# NodeMCU_Watering_System_III.net
KiCad netlist of a schematic drawn in EAGLE
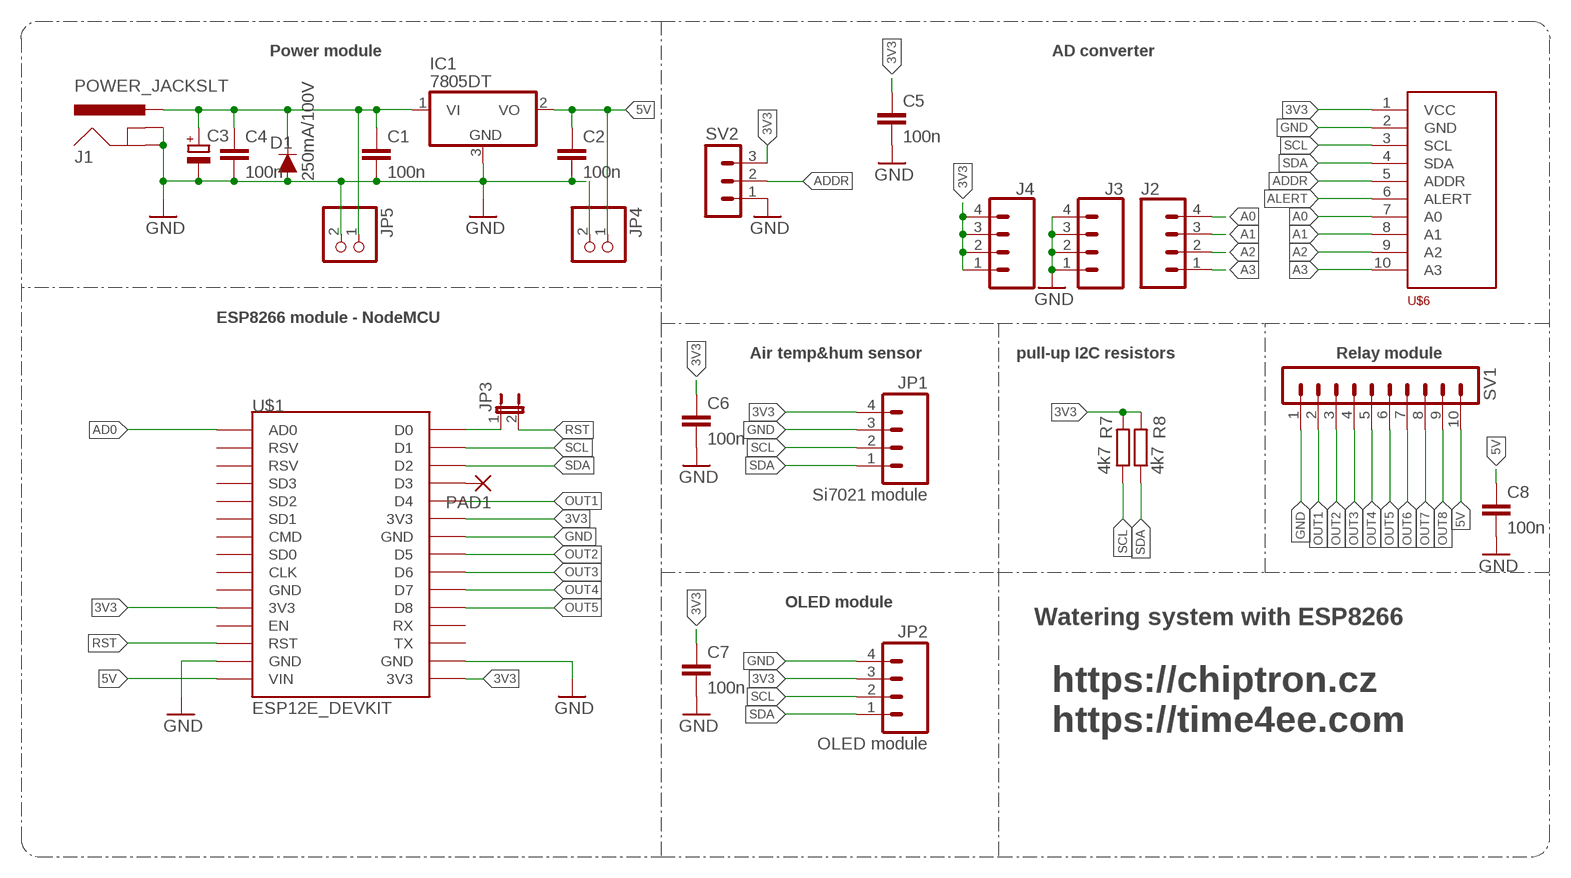
[diagram p0: schematic, sheet 1]

(export (version "E")
  (design (tool "Eeschema 10.0.6"))
  (components
    (comp (ref "C1")
      (value "100n")
      (footprint "eagle-import:C0805K")
      (libsource (lib "eagle-import") (part "C-EUC0805K"))
    )
    (comp (ref "C2")
      (value "100n")
      (footprint "eagle-import:C0805K")
      (libsource (lib "eagle-import") (part "C-EUC0805K"))
    )
    (comp (ref "C3")
      (value "CPOL-EUB/3528-21W")
      (footprint "eagle-import:B_3528-21W")
      (libsource (lib "eagle-import") (part "CPOL-EUB/3528-21W"))
    )
    (comp (ref "C4")
      (value "100n")
      (footprint "eagle-import:C0805K")
      (libsource (lib "eagle-import") (part "C-EUC0805K"))
    )
    (comp (ref "C5")
      (value "100n")
      (footprint "eagle-import:C0805K")
      (libsource (lib "eagle-import") (part "C-EUC0805K"))
    )
    (comp (ref "C6")
      (value "100n")
      (footprint "eagle-import:C0805K")
      (libsource (lib "eagle-import") (part "C-EUC0805K"))
    )
    (comp (ref "C7")
      (value "100n")
      (footprint "eagle-import:C0805K")
      (libsource (lib "eagle-import") (part "C-EUC0805K"))
    )
    (comp (ref "C8")
      (value "100n")
      (footprint "eagle-import:C0805K")
      (libsource (lib "eagle-import") (part "C-EUC0805K"))
    )
    (comp (ref "D1")
      (value "250mA/100V")
      (footprint "eagle-import:SOD-323")
      (libsource (lib "eagle-import") (part "DIODE-BAS16J"))
    )
    (comp (ref "IC1")
      (value "7805DT")
      (footprint "eagle-import:TO252")
      (libsource (lib "eagle-import") (part "78DT05"))
    )
    (comp (ref "J1")
      (value "POWER_JACKSLT")
      (footprint "eagle-import:POWER_JACK_SLOT")
      (libsource (lib "eagle-import") (part "POWER_JACKSLT"))
    )
    (comp (ref "J2")
      (value "CONN_04")
      (footprint "eagle-import:1X04")
      (libsource (lib "eagle-import") (part "CONN_04"))
    )
    (comp (ref "J3")
      (value "CONN_04")
      (footprint "eagle-import:1X04")
      (libsource (lib "eagle-import") (part "CONN_04"))
    )
    (comp (ref "J4")
      (value "CONN_04")
      (footprint "eagle-import:1X04")
      (libsource (lib "eagle-import") (part "CONN_04"))
    )
    (comp (ref "JP1")
      (value "Si7021 module")
      (footprint "eagle-import:1X04_LONGPADS")
      (libsource (lib "eagle-import") (part "M04LONGPADS"))
    )
    (comp (ref "JP2")
      (value "OLED module")
      (footprint "eagle-import:1X04_LONGPADS")
      (libsource (lib "eagle-import") (part "M04LONGPADS"))
    )
    (comp (ref "JP3")
      (value "JP1E")
      (footprint "eagle-import:JP1")
      (libsource (lib "eagle-import") (part "JP1E"))
    )
    (comp (ref "JP4")
      (value "PINHD-1X2")
      (footprint "eagle-import:1X02")
      (libsource (lib "eagle-import") (part "PINHD-1X2"))
    )
    (comp (ref "JP5")
      (value "PINHD-1X2")
      (footprint "eagle-import:1X02")
      (libsource (lib "eagle-import") (part "PINHD-1X2"))
    )
    (comp (ref "PAD1")
      (value "1,6/0,8")
      (footprint "eagle-import:1,6_0,8")
      (libsource (lib "eagle-import") (part "1,6/0,8"))
    )
    (comp (ref "R7")
      (value "4k7")
      (footprint "eagle-import:M0805")
      (libsource (lib "eagle-import") (part "R-EU_M0805"))
    )
    (comp (ref "R8")
      (value "4k7")
      (footprint "eagle-import:M0805")
      (libsource (lib "eagle-import") (part "R-EU_M0805"))
    )
    (comp (ref "SV1")
      (value "MA10-1")
      (footprint "eagle-import:MA10-1")
      (libsource (lib "eagle-import") (part "MA10-1"))
    )
    (comp (ref "SV2")
      (value "MA03-1")
      (footprint "eagle-import:MA03-1")
      (libsource (lib "eagle-import") (part "MA03-1"))
    )
    (comp (ref "U$1")
      (value "ESP12E_DEVKIT")
      (footprint "eagle-import:ESP12E_DEVKIT")
      (libsource (lib "eagle-import") (part "ESP12E_DEVKIT"))
    )
    (comp (ref "U$6")
      (value "ADS1115_BOARD")
      (footprint "eagle-import:ADS1115_ADS")
      (libsource (lib "eagle-import") (part "ADS1115_BOARD"))
    )
  )
  (nets
    (net (code "1") (name "3V3") (class "Default")
      (node (ref "C5") (pin "1") (pinfunction "1_1") (pintype "passive"))
      (node (ref "C6") (pin "1") (pinfunction "1_1") (pintype "passive"))
      (node (ref "C7") (pin "1") (pinfunction "1_1") (pintype "passive"))
      (node (ref "J4") (pin "1") (pinfunction "1_1") (pintype "passive"))
      (node (ref "J4") (pin "2") (pinfunction "2_2") (pintype "passive"))
      (node (ref "J4") (pin "3") (pinfunction "3_3") (pintype "passive"))
      (node (ref "J4") (pin "4") (pinfunction "4_4") (pintype "passive"))
      (node (ref "JP1") (pin "4") (pinfunction "4_4") (pintype "passive"))
      (node (ref "JP2") (pin "3") (pinfunction "3_3") (pintype "passive"))
      (node (ref "R7") (pin "2") (pinfunction "2_2") (pintype "passive"))
      (node (ref "R8") (pin "2") (pinfunction "2_2") (pintype "passive"))
      (node (ref "SV2") (pin "3") (pinfunction "3_3") (pintype "passive"))
      (node (ref "U$1") (pin "3V3@0") (pinfunction "3V3_3V3@0") (pintype "bidirectional"))
      (node (ref "U$1") (pin "3V3@1") (pinfunction "3V3_3V3@1") (pintype "bidirectional"))
      (node (ref "U$1") (pin "3V3@2") (pinfunction "3V3_3V3@2") (pintype "bidirectional"))
      (node (ref "U$6") (pin "1") (pinfunction "VCC_1") (pintype "bidirectional"))
    )
    (net (code "2") (name "5V") (class "Default")
      (node (ref "C2") (pin "1") (pinfunction "1_1") (pintype "passive"))
      (node (ref "C8") (pin "1") (pinfunction "1_1") (pintype "passive"))
      (node (ref "IC1") (pin "2") (pinfunction "VO_2") (pintype "passive"))
      (node (ref "JP4") (pin "1") (pinfunction "1_1") (pintype "passive"))
      (node (ref "SV1") (pin "10") (pinfunction "10_10") (pintype "passive"))
      (node (ref "U$1") (pin "VIN") (pinfunction "VIN_VIN") (pintype "bidirectional"))
    )
    (net (code "3") (name "A0") (class "Default")
      (node (ref "J2") (pin "4") (pinfunction "4_4") (pintype "passive"))
      (node (ref "U$6") (pin "7") (pinfunction "A0_7") (pintype "bidirectional"))
    )
    (net (code "4") (name "A1") (class "Default")
      (node (ref "J2") (pin "3") (pinfunction "3_3") (pintype "passive"))
      (node (ref "U$6") (pin "8") (pinfunction "A1_8") (pintype "bidirectional"))
    )
    (net (code "5") (name "A2") (class "Default")
      (node (ref "J2") (pin "2") (pinfunction "2_2") (pintype "passive"))
      (node (ref "U$6") (pin "9") (pinfunction "A2_9") (pintype "bidirectional"))
    )
    (net (code "6") (name "A3") (class "Default")
      (node (ref "J2") (pin "1") (pinfunction "1_1") (pintype "passive"))
      (node (ref "U$6") (pin "10") (pinfunction "A3_10") (pintype "bidirectional"))
    )
    (net (code "7") (name "AD0") (class "Default")
      (node (ref "U$1") (pin "AD0") (pinfunction "AD0_AD0") (pintype "bidirectional"))
    )
    (net (code "8") (name "ADDR") (class "Default")
      (node (ref "SV2") (pin "2") (pinfunction "2_2") (pintype "passive"))
      (node (ref "U$6") (pin "5") (pinfunction "ADDR_5") (pintype "bidirectional"))
    )
    (net (code "9") (name "ALERT") (class "Default")
      (node (ref "U$6") (pin "6") (pinfunction "ALERT_6") (pintype "bidirectional"))
    )
    (net (code "10") (name "GND") (class "Default")
      (node (ref "C1") (pin "2") (pinfunction "2_2") (pintype "passive"))
      (node (ref "C2") (pin "2") (pinfunction "2_2") (pintype "passive"))
      (node (ref "C3") (pin "-") (pinfunction "-_-") (pintype "passive"))
      (node (ref "C4") (pin "2") (pinfunction "2_2") (pintype "passive"))
      (node (ref "C5") (pin "2") (pinfunction "2_2") (pintype "passive"))
      (node (ref "C6") (pin "2") (pinfunction "2_2") (pintype "passive"))
      (node (ref "C7") (pin "2") (pinfunction "2_2") (pintype "passive"))
      (node (ref "C8") (pin "2") (pinfunction "2_2") (pintype "passive"))
      (node (ref "D1") (pin "A") (pinfunction "A_A") (pintype "passive"))
      (node (ref "IC1") (pin "3") (pinfunction "GND_3") (pintype "passive"))
      (node (ref "J1") (pin "GND@1") (pinfunction "GNDBREAK_GND@1") (pintype "bidirectional"))
      (node (ref "J1") (pin "GND@2") (pinfunction "GND_GND@2") (pintype "bidirectional"))
      (node (ref "J3") (pin "1") (pinfunction "1_1") (pintype "passive"))
      (node (ref "J3") (pin "2") (pinfunction "2_2") (pintype "passive"))
      (node (ref "J3") (pin "3") (pinfunction "3_3") (pintype "passive"))
      (node (ref "J3") (pin "4") (pinfunction "4_4") (pintype "passive"))
      (node (ref "JP1") (pin "3") (pinfunction "3_3") (pintype "passive"))
      (node (ref "JP2") (pin "4") (pinfunction "4_4") (pintype "passive"))
      (node (ref "JP4") (pin "2") (pinfunction "2_2") (pintype "passive"))
      (node (ref "JP5") (pin "2") (pinfunction "2_2") (pintype "passive"))
      (node (ref "SV1") (pin "1") (pinfunction "1_1") (pintype "passive"))
      (node (ref "SV2") (pin "1") (pinfunction "1_1") (pintype "passive"))
      (node (ref "U$1") (pin "GND@1") (pinfunction "GND_GND@1") (pintype "bidirectional"))
      (node (ref "U$1") (pin "GND@2") (pinfunction "GND_GND@2") (pintype "bidirectional"))
      (node (ref "U$1") (pin "GND@3") (pinfunction "GND_GND@3") (pintype "bidirectional"))
      (node (ref "U$6") (pin "2") (pinfunction "GND_2") (pintype "bidirectional"))
    )
    (net (code "11") (name "Net-(IC1-VI)") (class "Default")
      (node (ref "C1") (pin "1") (pinfunction "1_1") (pintype "passive"))
      (node (ref "C3") (pin "+") (pinfunction "+_+") (pintype "passive"))
      (node (ref "C4") (pin "1") (pinfunction "1_1") (pintype "passive"))
      (node (ref "D1") (pin "C") (pinfunction "C_C") (pintype "passive"))
      (node (ref "IC1") (pin "1") (pinfunction "VI_1") (pintype "input"))
      (node (ref "J1") (pin "PWR") (pinfunction "PWR_PWR") (pintype "bidirectional"))
      (node (ref "JP5") (pin "1") (pinfunction "1_1") (pintype "passive"))
    )
    (net (code "12") (name "Net-(JP3-Pad1)") (class "Default")
      (node (ref "JP3") (pin "1") (pinfunction "1_1") (pintype "passive"))
      (node (ref "U$1") (pin "D0") (pinfunction "D0_D0") (pintype "bidirectional"))
    )
    (net (code "13") (name "Net-(PAD1-P)") (class "Default")
      (node (ref "PAD1") (pin "1") (pinfunction "P_1") (pintype "passive"))
      (node (ref "U$1") (pin "D3") (pinfunction "D3_D3") (pintype "bidirectional"))
    )
    (net (code "14") (name "OUT1") (class "Default")
      (node (ref "SV1") (pin "2") (pinfunction "2_2") (pintype "passive"))
      (node (ref "U$1") (pin "D4") (pinfunction "D4_D4") (pintype "bidirectional"))
    )
    (net (code "15") (name "OUT2") (class "Default")
      (node (ref "SV1") (pin "3") (pinfunction "3_3") (pintype "passive"))
      (node (ref "U$1") (pin "D5") (pinfunction "D5_D5") (pintype "bidirectional"))
    )
    (net (code "16") (name "OUT3") (class "Default")
      (node (ref "SV1") (pin "4") (pinfunction "4_4") (pintype "passive"))
      (node (ref "U$1") (pin "D6") (pinfunction "D6_D6") (pintype "bidirectional"))
    )
    (net (code "17") (name "OUT4") (class "Default")
      (node (ref "SV1") (pin "5") (pinfunction "5_5") (pintype "passive"))
      (node (ref "U$1") (pin "D7") (pinfunction "D7_D7") (pintype "bidirectional"))
    )
    (net (code "18") (name "OUT5") (class "Default")
      (node (ref "SV1") (pin "6") (pinfunction "6_6") (pintype "passive"))
      (node (ref "U$1") (pin "D8") (pinfunction "D8_D8") (pintype "bidirectional"))
    )
    (net (code "19") (name "OUT6") (class "Default")
      (node (ref "SV1") (pin "7") (pinfunction "7_7") (pintype "passive"))
    )
    (net (code "20") (name "OUT7") (class "Default")
      (node (ref "SV1") (pin "8") (pinfunction "8_8") (pintype "passive"))
    )
    (net (code "21") (name "OUT8") (class "Default")
      (node (ref "SV1") (pin "9") (pinfunction "9_9") (pintype "passive"))
    )
    (net (code "22") (name "RST") (class "Default")
      (node (ref "JP3") (pin "2") (pinfunction "2_2") (pintype "passive"))
      (node (ref "U$1") (pin "RST") (pinfunction "RST_RST") (pintype "bidirectional"))
    )
    (net (code "23") (name "SCL") (class "Default")
      (node (ref "JP1") (pin "2") (pinfunction "2_2") (pintype "passive"))
      (node (ref "JP2") (pin "2") (pinfunction "2_2") (pintype "passive"))
      (node (ref "R7") (pin "1") (pinfunction "1_1") (pintype "passive"))
      (node (ref "U$1") (pin "D1") (pinfunction "D1_D1") (pintype "bidirectional"))
      (node (ref "U$6") (pin "3") (pinfunction "SCL_3") (pintype "bidirectional"))
    )
    (net (code "24") (name "SDA") (class "Default")
      (node (ref "JP1") (pin "1") (pinfunction "1_1") (pintype "passive"))
      (node (ref "JP2") (pin "1") (pinfunction "1_1") (pintype "passive"))
      (node (ref "R8") (pin "1") (pinfunction "1_1") (pintype "passive"))
      (node (ref "U$1") (pin "D2") (pinfunction "D2_D2") (pintype "bidirectional"))
      (node (ref "U$6") (pin "4") (pinfunction "SDA_4") (pintype "bidirectional"))
    )
    (net (code "25") (name "unconnected-(U$1-GND-PadGND@0)") (class "Default")
      (node (ref "U$1") (pin "GND@0") (pinfunction "GND_GND@0") (pintype "bidirectional"))
    )
    (net (code "26") (name "unconnected-(U$1-PadCLK)") (class "Default")
      (node (ref "U$1") (pin "CLK") (pinfunction "CLK_CLK") (pintype "bidirectional"))
    )
    (net (code "27") (name "unconnected-(U$1-PadCMD)") (class "Default")
      (node (ref "U$1") (pin "CMD") (pinfunction "CMD_CMD") (pintype "bidirectional"))
    )
    (net (code "28") (name "unconnected-(U$1-PadEN)") (class "Default")
      (node (ref "U$1") (pin "EN") (pinfunction "EN_EN") (pintype "bidirectional"))
    )
    (net (code "29") (name "unconnected-(U$1-PadRX)") (class "Default")
      (node (ref "U$1") (pin "RX") (pinfunction "RX_RX") (pintype "bidirectional"))
    )
    (net (code "30") (name "unconnected-(U$1-PadSD0)") (class "Default")
      (node (ref "U$1") (pin "SD0") (pinfunction "SD0_SD0") (pintype "bidirectional"))
    )
    (net (code "31") (name "unconnected-(U$1-PadSD1)") (class "Default")
      (node (ref "U$1") (pin "SD1") (pinfunction "SD1_SD1") (pintype "bidirectional"))
    )
    (net (code "32") (name "unconnected-(U$1-PadSD2)") (class "Default")
      (node (ref "U$1") (pin "SD2") (pinfunction "SD2_SD2") (pintype "bidirectional"))
    )
    (net (code "33") (name "unconnected-(U$1-PadSD3)") (class "Default")
      (node (ref "U$1") (pin "SD3") (pinfunction "SD3_SD3") (pintype "bidirectional"))
    )
    (net (code "34") (name "unconnected-(U$1-PadTX)") (class "Default")
      (node (ref "U$1") (pin "TX") (pinfunction "TX_TX") (pintype "bidirectional"))
    )
    (net (code "35") (name "unconnected-(U$1-RSV-PadRSV@0)") (class "Default")
      (node (ref "U$1") (pin "RSV@0") (pinfunction "RSV_RSV@0") (pintype "bidirectional"))
    )
    (net (code "36") (name "unconnected-(U$1-RSV-PadRSV@1)") (class "Default")
      (node (ref "U$1") (pin "RSV@1") (pinfunction "RSV_RSV@1") (pintype "bidirectional"))
    )
  )
)
